# mt10.net
KiCad netlist of a schematic drawn in EAGLE
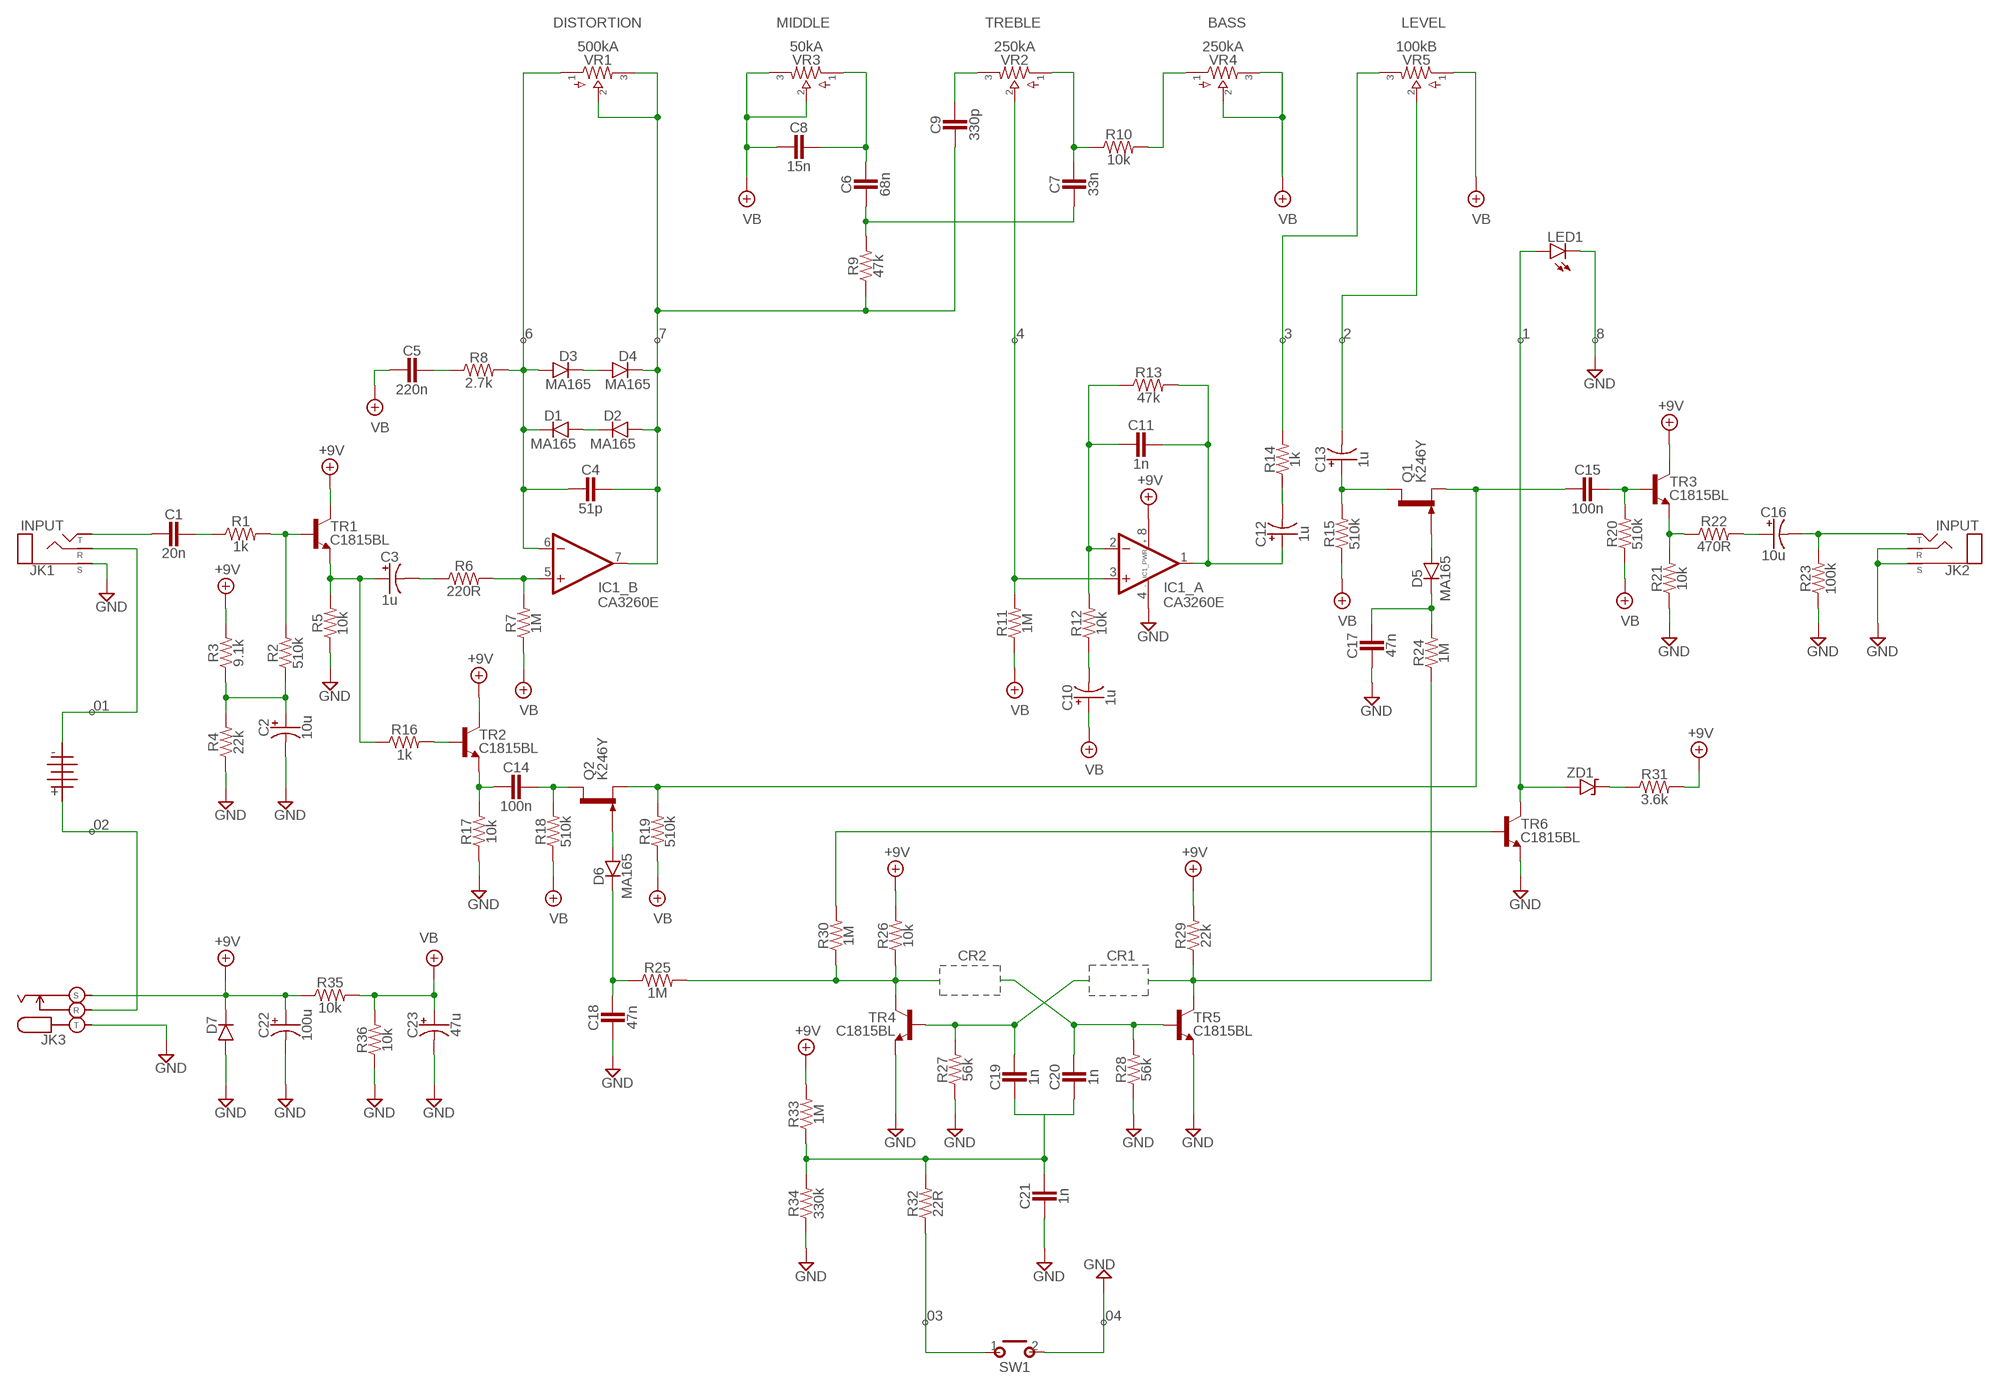
[diagram p0: schematic, sheet 1]

(export (version "E")
  (design (tool "Eeschema 10.0.6"))
  (components
    (comp (ref "1101")
      (value "BATTERY")
      (footprint "eagle-import:TWO_PADS")
      (libsource (lib "eagle-import") (part "BATTERY"))
    )
    (comp (ref "C1")
      (value "20n")
      (footprint "eagle-import:BOX_SMALL")
      (libsource (lib "eagle-import") (part "CER/FILMBOX.1"))
    )
    (comp (ref "C2")
      (value "10u")
      (footprint "eagle-import:050_020")
      (libsource (lib "eagle-import") (part "0500"))
    )
    (comp (ref "C3")
      (value "1u")
      (footprint "eagle-import:050_020")
      (libsource (lib "eagle-import") (part "0500"))
    )
    (comp (ref "C4")
      (value "51p")
      (footprint "eagle-import:BOX_SMALL")
      (libsource (lib "eagle-import") (part "CER/FILMBOX.1"))
    )
    (comp (ref "C5")
      (value "220n")
      (footprint "eagle-import:BOX_SMALL")
      (libsource (lib "eagle-import") (part "CER/FILMBOX.1"))
    )
    (comp (ref "C6")
      (value "68n")
      (footprint "eagle-import:BOX_SMALL")
      (libsource (lib "eagle-import") (part "CER/FILMBOX.1"))
    )
    (comp (ref "C7")
      (value "33n")
      (footprint "eagle-import:BOX_SMALL")
      (libsource (lib "eagle-import") (part "CER/FILMBOX.1"))
    )
    (comp (ref "C8")
      (value "15n")
      (footprint "eagle-import:BOX_SMALL")
      (libsource (lib "eagle-import") (part "CER/FILMBOX.1"))
    )
    (comp (ref "C9")
      (value "330p")
      (footprint "eagle-import:BOX_SMALL")
      (libsource (lib "eagle-import") (part "CER/FILMBOX.1"))
    )
    (comp (ref "C10")
      (value "1u")
      (footprint "eagle-import:050_020")
      (libsource (lib "eagle-import") (part "0500"))
    )
    (comp (ref "C11")
      (value "1n")
      (footprint "eagle-import:BOX_SMALL")
      (libsource (lib "eagle-import") (part "CER/FILMBOX.1"))
    )
    (comp (ref "C12")
      (value "1u")
      (footprint "eagle-import:050_020")
      (libsource (lib "eagle-import") (part "0500"))
    )
    (comp (ref "C13")
      (value "1u")
      (footprint "eagle-import:050_020")
      (libsource (lib "eagle-import") (part "0500"))
    )
    (comp (ref "C14")
      (value "100n")
      (footprint "eagle-import:BOX_SMALL")
      (libsource (lib "eagle-import") (part "CER/FILMBOX.1"))
    )
    (comp (ref "C15")
      (value "100n")
      (footprint "eagle-import:BOX_SMALL")
      (libsource (lib "eagle-import") (part "CER/FILMBOX.1"))
    )
    (comp (ref "C16")
      (value "10u")
      (footprint "eagle-import:050_020")
      (libsource (lib "eagle-import") (part "0500"))
    )
    (comp (ref "C17")
      (value "47n")
      (footprint "eagle-import:BOX_SMALL")
      (libsource (lib "eagle-import") (part "CER/FILMBOX.1"))
    )
    (comp (ref "C18")
      (value "47n")
      (footprint "eagle-import:BOX_SMALL")
      (libsource (lib "eagle-import") (part "CER/FILMBOX.1"))
    )
    (comp (ref "C19")
      (value "1n")
      (footprint "eagle-import:BOX_SMALL")
      (libsource (lib "eagle-import") (part "CER/FILMBOX.1"))
    )
    (comp (ref "C20")
      (value "1n")
      (footprint "eagle-import:BOX_SMALL")
      (libsource (lib "eagle-import") (part "CER/FILMBOX.1"))
    )
    (comp (ref "C21")
      (value "1n")
      (footprint "eagle-import:BOX_SMALL")
      (libsource (lib "eagle-import") (part "CER/FILMBOX.1"))
    )
    (comp (ref "C22")
      (value "100u")
      (footprint "eagle-import:050_020")
      (libsource (lib "eagle-import") (part "0500"))
    )
    (comp (ref "C23")
      (value "47u")
      (footprint "eagle-import:050_020")
      (libsource (lib "eagle-import") (part "0500"))
    )
    (comp (ref "D1")
      (value "MA165")
      (footprint "eagle-import:DO35-2")
      (libsource (lib "eagle-import") (part "DO35.2"))
    )
    (comp (ref "D2")
      (value "MA165")
      (footprint "eagle-import:DO35-2")
      (libsource (lib "eagle-import") (part "DO35.2"))
    )
    (comp (ref "D3")
      (value "MA165")
      (footprint "eagle-import:DO35-2")
      (libsource (lib "eagle-import") (part "DO35.2"))
    )
    (comp (ref "D4")
      (value "MA165")
      (footprint "eagle-import:DO35-2")
      (libsource (lib "eagle-import") (part "DO35.2"))
    )
    (comp (ref "D5")
      (value "MA165")
      (footprint "eagle-import:DO35-2")
      (libsource (lib "eagle-import") (part "DO35.2"))
    )
    (comp (ref "D6")
      (value "MA165")
      (footprint "eagle-import:DO35-2")
      (libsource (lib "eagle-import") (part "DO35.2"))
    )
    (comp (ref "D7")
      (value "DO35.2")
      (footprint "eagle-import:DO35-2")
      (libsource (lib "eagle-import") (part "DO35.2"))
    )
    (comp (ref "IC1")
      (value "CA3260E")
      (footprint "eagle-import:DIL0")
      (libsource (lib "eagle-import") (part "DUALTH"))
    )
    (comp (ref "JK1")
      (value "INPUT")
      (footprint "eagle-import:THREEPADS")
      (libsource (lib "eagle-import") (part "STEREO3PADS"))
    )
    (comp (ref "JK2")
      (value "INPUT")
      (footprint "eagle-import:THREEPADS")
      (libsource (lib "eagle-import") (part "STEREO3PADS"))
    )
    (comp (ref "JK3")
      (value "DCJACK")
      (footprint "eagle-import:DC_KOBICONN")
      (libsource (lib "eagle-import") (part "DC_KOBICONN"))
    )
    (comp (ref "LED1")
      (value "LED")
      (footprint "eagle-import:3MM_D")
      (libsource (lib "eagle-import") (part "LED"))
    )
    (comp (ref "Q1")
      (value "K246Y")
      (footprint "eagle-import:TO92-")
      (libsource (lib "eagle-import") (part "2N5457"))
    )
    (comp (ref "Q2")
      (value "K246Y")
      (footprint "eagle-import:TO92-")
      (libsource (lib "eagle-import") (part "2N5457"))
    )
    (comp (ref "R1")
      (value "1k")
      (footprint "eagle-import:R0207_3")
      (libsource (lib "eagle-import") (part "R_.3B"))
    )
    (comp (ref "R2")
      (value "510k")
      (footprint "eagle-import:R0207_3")
      (libsource (lib "eagle-import") (part "R_.3B"))
    )
    (comp (ref "R3")
      (value "9.1k")
      (footprint "eagle-import:R0207_3")
      (libsource (lib "eagle-import") (part "R_.3B"))
    )
    (comp (ref "R4")
      (value "22k")
      (footprint "eagle-import:R0207_3")
      (libsource (lib "eagle-import") (part "R_.3B"))
    )
    (comp (ref "R5")
      (value "10k")
      (footprint "eagle-import:R0207_3")
      (libsource (lib "eagle-import") (part "R_.3B"))
    )
    (comp (ref "R6")
      (value "220R")
      (footprint "eagle-import:R0207_3")
      (libsource (lib "eagle-import") (part "R_.3B"))
    )
    (comp (ref "R7")
      (value "1M")
      (footprint "eagle-import:R0207_3")
      (libsource (lib "eagle-import") (part "R_.3B"))
    )
    (comp (ref "R8")
      (value "2.7k")
      (footprint "eagle-import:R0207_3")
      (libsource (lib "eagle-import") (part "R_.3B"))
    )
    (comp (ref "R9")
      (value "47k")
      (footprint "eagle-import:R0207_3")
      (libsource (lib "eagle-import") (part "R_.3B"))
    )
    (comp (ref "R10")
      (value "10k")
      (footprint "eagle-import:R0207_3")
      (libsource (lib "eagle-import") (part "R_.3B"))
    )
    (comp (ref "R11")
      (value "1M")
      (footprint "eagle-import:R0207_3")
      (libsource (lib "eagle-import") (part "R_.3B"))
    )
    (comp (ref "R12")
      (value "10k")
      (footprint "eagle-import:R0207_3")
      (libsource (lib "eagle-import") (part "R_.3B"))
    )
    (comp (ref "R13")
      (value "47k")
      (footprint "eagle-import:R0207_3")
      (libsource (lib "eagle-import") (part "R_.3B"))
    )
    (comp (ref "R14")
      (value "1k")
      (footprint "eagle-import:R0207_3")
      (libsource (lib "eagle-import") (part "R_.3B"))
    )
    (comp (ref "R15")
      (value "510k")
      (footprint "eagle-import:R0207_3")
      (libsource (lib "eagle-import") (part "R_.3B"))
    )
    (comp (ref "R16")
      (value "1k")
      (footprint "eagle-import:R0207_3")
      (libsource (lib "eagle-import") (part "R_.3B"))
    )
    (comp (ref "R17")
      (value "10k")
      (footprint "eagle-import:R0207_3")
      (libsource (lib "eagle-import") (part "R_.3B"))
    )
    (comp (ref "R18")
      (value "510k")
      (footprint "eagle-import:R0207_3")
      (libsource (lib "eagle-import") (part "R_.3B"))
    )
    (comp (ref "R19")
      (value "510k")
      (footprint "eagle-import:R0207_3")
      (libsource (lib "eagle-import") (part "R_.3B"))
    )
    (comp (ref "R20")
      (value "510k")
      (footprint "eagle-import:R0207_3")
      (libsource (lib "eagle-import") (part "R_.3B"))
    )
    (comp (ref "R21")
      (value "10k")
      (footprint "eagle-import:R0207_3")
      (libsource (lib "eagle-import") (part "R_.3B"))
    )
    (comp (ref "R22")
      (value "470R")
      (footprint "eagle-import:R0207_3")
      (libsource (lib "eagle-import") (part "R_.3B"))
    )
    (comp (ref "R23")
      (value "100k")
      (footprint "eagle-import:R0207_3")
      (libsource (lib "eagle-import") (part "R_.3B"))
    )
    (comp (ref "R24")
      (value "1M")
      (footprint "eagle-import:R0207_3")
      (libsource (lib "eagle-import") (part "R_.3B"))
    )
    (comp (ref "R25")
      (value "1M")
      (footprint "eagle-import:R0207_3")
      (libsource (lib "eagle-import") (part "R_.3B"))
    )
    (comp (ref "R26")
      (value "10k")
      (footprint "eagle-import:R0207_3")
      (libsource (lib "eagle-import") (part "R_.3B"))
    )
    (comp (ref "R27")
      (value "56k")
      (footprint "eagle-import:R0207_3")
      (libsource (lib "eagle-import") (part "R_.3B"))
    )
    (comp (ref "R28")
      (value "56k")
      (footprint "eagle-import:R0207_3")
      (libsource (lib "eagle-import") (part "R_.3B"))
    )
    (comp (ref "R29")
      (value "22k")
      (footprint "eagle-import:R0207_3")
      (libsource (lib "eagle-import") (part "R_.3B"))
    )
    (comp (ref "R30")
      (value "1M")
      (footprint "eagle-import:R0207_3")
      (libsource (lib "eagle-import") (part "R_.3B"))
    )
    (comp (ref "R31")
      (value "3.6k")
      (footprint "eagle-import:R0207_3")
      (libsource (lib "eagle-import") (part "R_.3B"))
    )
    (comp (ref "R32")
      (value "22R")
      (footprint "eagle-import:R0207_3")
      (libsource (lib "eagle-import") (part "R_.3B"))
    )
    (comp (ref "R33")
      (value "1M")
      (footprint "eagle-import:R0207_3")
      (libsource (lib "eagle-import") (part "R_.3B"))
    )
    (comp (ref "R34")
      (value "330k")
      (footprint "eagle-import:R0207_3")
      (libsource (lib "eagle-import") (part "R_.3B"))
    )
    (comp (ref "R35")
      (value "10k")
      (footprint "eagle-import:R0207_3")
      (libsource (lib "eagle-import") (part "R_.3B"))
    )
    (comp (ref "R36")
      (value "10k")
      (footprint "eagle-import:R0207_3")
      (libsource (lib "eagle-import") (part "R_.3B"))
    )
    (comp (ref "SW1")
      (value "MOMENTARY")
      (footprint "eagle-import:SPST")
      (libsource (lib "eagle-import") (part "MOMENTARY"))
    )
    (comp (ref "TR1")
      (value "C1815BL")
      (footprint "eagle-import:TO92-")
      (libsource (lib "eagle-import") (part "2SC828A"))
    )
    (comp (ref "TR2")
      (value "C1815BL")
      (footprint "eagle-import:TO92-")
      (libsource (lib "eagle-import") (part "2SC828A"))
    )
    (comp (ref "TR3")
      (value "C1815BL")
      (footprint "eagle-import:TO92-")
      (libsource (lib "eagle-import") (part "2SC828A"))
    )
    (comp (ref "TR4")
      (value "C1815BL")
      (footprint "eagle-import:TO92-")
      (libsource (lib "eagle-import") (part "2SC828A"))
    )
    (comp (ref "TR5")
      (value "C1815BL")
      (footprint "eagle-import:TO92-")
      (libsource (lib "eagle-import") (part "2SC828A"))
    )
    (comp (ref "TR6")
      (value "C1815BL")
      (footprint "eagle-import:TO92-")
      (libsource (lib "eagle-import") (part "2SC828A"))
    )
    (comp (ref "VR1")
      (value "500kA")
      (footprint "eagle-import:16MM")
      (libsource (lib "eagle-import") (part "POTS16MM"))
    )
    (comp (ref "VR2")
      (value "250kA")
      (footprint "eagle-import:16MM")
      (libsource (lib "eagle-import") (part "POTS16MM"))
    )
    (comp (ref "VR3")
      (value "50kA")
      (footprint "eagle-import:16MM")
      (libsource (lib "eagle-import") (part "POTS16MM"))
    )
    (comp (ref "VR4")
      (value "250kA")
      (footprint "eagle-import:16MM")
      (libsource (lib "eagle-import") (part "POTS16MM"))
    )
    (comp (ref "VR5")
      (value "100kB")
      (footprint "eagle-import:16MM")
      (libsource (lib "eagle-import") (part "POTS16MM"))
    )
    (comp (ref "ZD1")
      (value "ZENER.1")
      (footprint "eagle-import:DO41-1")
      (libsource (lib "eagle-import") (part "ZENER.1"))
    )
  )
  (nets
    (net (code "1") (name "+9V") (class "Default")
      (node (ref "C22") (pin "+") (pinfunction "+_+") (pintype "passive"))
      (node (ref "D7") (pin "C") (pinfunction "C_C") (pintype "passive"))
      (node (ref "IC1") (pin "8") (pinfunction "V+_8") (pintype "power_in"))
      (node (ref "JK3") (pin "S") (pinfunction "S_S") (pintype "bidirectional"))
      (node (ref "R26") (pin "2") (pinfunction "2_2") (pintype "passive"))
      (node (ref "R29") (pin "2") (pinfunction "2_2") (pintype "passive"))
      (node (ref "R3") (pin "2") (pinfunction "2_2") (pintype "passive"))
      (node (ref "R31") (pin "2") (pinfunction "2_2") (pintype "passive"))
      (node (ref "R33") (pin "2") (pinfunction "2_2") (pintype "passive"))
      (node (ref "R35") (pin "1") (pinfunction "1_1") (pintype "passive"))
      (node (ref "TR1") (pin "2") (pinfunction "C_2") (pintype "passive"))
      (node (ref "TR2") (pin "2") (pinfunction "C_2") (pintype "passive"))
      (node (ref "TR3") (pin "2") (pinfunction "C_2") (pintype "passive"))
    )
    (net (code "2") (name "GND") (class "Default")
      (node (ref "C17") (pin "2") (pinfunction "2_2") (pintype "passive"))
      (node (ref "C18") (pin "2") (pinfunction "2_2") (pintype "passive"))
      (node (ref "C2") (pin "-") (pinfunction "-_-") (pintype "passive"))
      (node (ref "C21") (pin "2") (pinfunction "2_2") (pintype "passive"))
      (node (ref "C22") (pin "-") (pinfunction "-_-") (pintype "passive"))
      (node (ref "C23") (pin "-") (pinfunction "-_-") (pintype "passive"))
      (node (ref "D7") (pin "A") (pinfunction "A_A") (pintype "passive"))
      (node (ref "IC1") (pin "4") (pinfunction "V-_4") (pintype "power_in"))
      (node (ref "JK1") (pin "SLEEVE") (pinfunction "S_SLEEVE") (pintype "passive"))
      (node (ref "JK2") (pin "RING") (pinfunction "R_RING") (pintype "passive"))
      (node (ref "JK2") (pin "SLEEVE") (pinfunction "S_SLEEVE") (pintype "passive"))
      (node (ref "JK3") (pin "T") (pinfunction "T_T") (pintype "bidirectional"))
      (node (ref "LED1") (pin "P$1") (pinfunction "C_P$1") (pintype "passive"))
      (node (ref "R17") (pin "1") (pinfunction "1_1") (pintype "passive"))
      (node (ref "R21") (pin "1") (pinfunction "1_1") (pintype "passive"))
      (node (ref "R23") (pin "1") (pinfunction "1_1") (pintype "passive"))
      (node (ref "R27") (pin "1") (pinfunction "1_1") (pintype "passive"))
      (node (ref "R28") (pin "1") (pinfunction "1_1") (pintype "passive"))
      (node (ref "R34") (pin "1") (pinfunction "1_1") (pintype "passive"))
      (node (ref "R36") (pin "1") (pinfunction "1_1") (pintype "passive"))
      (node (ref "R4") (pin "1") (pinfunction "1_1") (pintype "passive"))
      (node (ref "R5") (pin "1") (pinfunction "1_1") (pintype "passive"))
      (node (ref "SW1") (pin "2") (pinfunction "S_2") (pintype "passive"))
      (node (ref "TR4") (pin "3") (pinfunction "E_3") (pintype "passive"))
      (node (ref "TR5") (pin "3") (pinfunction "E_3") (pintype "passive"))
      (node (ref "TR6") (pin "3") (pinfunction "E_3") (pintype "passive"))
    )
    (net (code "3") (name "Net-(1101-P$1)") (class "Default")
      (node (ref "1101") (pin "T") (pinfunction "P$1_T") (pintype "bidirectional"))
      (node (ref "JK3") (pin "R") (pinfunction "R_R") (pintype "bidirectional"))
    )
    (net (code "4") (name "Net-(1101-P$2)") (class "Default")
      (node (ref "1101") (pin "S") (pinfunction "P$2_S") (pintype "bidirectional"))
      (node (ref "JK1") (pin "RING") (pinfunction "R_RING") (pintype "passive"))
    )
    (net (code "5") (name "Net-(C1-Pad1)") (class "Default")
      (node (ref "C1") (pin "1") (pinfunction "1_1") (pintype "passive"))
      (node (ref "R1") (pin "1") (pinfunction "1_1") (pintype "passive"))
    )
    (net (code "6") (name "Net-(C2-Pad+)") (class "Default")
      (node (ref "C2") (pin "+") (pinfunction "+_+") (pintype "passive"))
      (node (ref "R2") (pin "1") (pinfunction "1_1") (pintype "passive"))
      (node (ref "R3") (pin "1") (pinfunction "1_1") (pintype "passive"))
      (node (ref "R4") (pin "2") (pinfunction "2_2") (pintype "passive"))
    )
    (net (code "7") (name "Net-(C3-Pad-)") (class "Default")
      (node (ref "C3") (pin "-") (pinfunction "-_-") (pintype "passive"))
      (node (ref "R6") (pin "1") (pinfunction "1_1") (pintype "passive"))
    )
    (net (code "8") (name "Net-(C5-Pad1)") (class "Default")
      (node (ref "C5") (pin "1") (pinfunction "1_1") (pintype "passive"))
      (node (ref "R8") (pin "1") (pinfunction "1_1") (pintype "passive"))
    )
    (net (code "9") (name "Net-(C6-Pad1)") (class "Default")
      (node (ref "C6") (pin "1") (pinfunction "1_1") (pintype "passive"))
      (node (ref "C8") (pin "1") (pinfunction "1_1") (pintype "passive"))
      (node (ref "VR3") (pin "1") (pinfunction "1_1") (pintype "passive"))
    )
    (net (code "10") (name "Net-(C6-Pad2)") (class "Default")
      (node (ref "C6") (pin "2") (pinfunction "2_2") (pintype "passive"))
      (node (ref "C7") (pin "2") (pinfunction "2_2") (pintype "passive"))
      (node (ref "R9") (pin "2") (pinfunction "2_2") (pintype "passive"))
    )
    (net (code "11") (name "Net-(C7-Pad1)") (class "Default")
      (node (ref "C7") (pin "1") (pinfunction "1_1") (pintype "passive"))
      (node (ref "R10") (pin "1") (pinfunction "1_1") (pintype "passive"))
      (node (ref "VR2") (pin "1") (pinfunction "1_1") (pintype "passive"))
    )
    (net (code "12") (name "Net-(C9-Pad1)") (class "Default")
      (node (ref "C9") (pin "1") (pinfunction "1_1") (pintype "passive"))
      (node (ref "VR2") (pin "3") (pinfunction "3_3") (pintype "passive"))
    )
    (net (code "13") (name "Net-(C10-Pad-)") (class "Default")
      (node (ref "C10") (pin "-") (pinfunction "-_-") (pintype "passive"))
      (node (ref "R12") (pin "1") (pinfunction "1_1") (pintype "passive"))
    )
    (net (code "14") (name "Net-(C12-Pad-)") (class "Default")
      (node (ref "C12") (pin "-") (pinfunction "-_-") (pintype "passive"))
      (node (ref "R14") (pin "1") (pinfunction "1_1") (pintype "passive"))
    )
    (net (code "15") (name "Net-(C13-Pad-)") (class "Default")
      (node (ref "C13") (pin "-") (pinfunction "-_-") (pintype "passive"))
      (node (ref "VR5") (pin "2") (pinfunction "2_2") (pintype "passive"))
    )
    (net (code "16") (name "Net-(C16-Pad+)") (class "Default")
      (node (ref "C16") (pin "+") (pinfunction "+_+") (pintype "passive"))
      (node (ref "R22") (pin "2") (pinfunction "2_2") (pintype "passive"))
    )
    (net (code "17") (name "Net-(C17-Pad1)") (class "Default")
      (node (ref "C17") (pin "1") (pinfunction "1_1") (pintype "passive"))
      (node (ref "D5") (pin "C") (pinfunction "C_C") (pintype "passive"))
      (node (ref "R24") (pin "2") (pinfunction "2_2") (pintype "passive"))
    )
    (net (code "18") (name "Net-(C18-Pad1)") (class "Default")
      (node (ref "C18") (pin "1") (pinfunction "1_1") (pintype "passive"))
      (node (ref "D6") (pin "C") (pinfunction "C_C") (pintype "passive"))
      (node (ref "R25") (pin "1") (pinfunction "1_1") (pintype "passive"))
    )
    (net (code "19") (name "Net-(C19-Pad2)") (class "Default")
      (node (ref "C19") (pin "2") (pinfunction "2_2") (pintype "passive"))
      (node (ref "C20") (pin "2") (pinfunction "2_2") (pintype "passive"))
      (node (ref "C21") (pin "1") (pinfunction "1_1") (pintype "passive"))
      (node (ref "R32") (pin "2") (pinfunction "2_2") (pintype "passive"))
      (node (ref "R33") (pin "1") (pinfunction "1_1") (pintype "passive"))
      (node (ref "R34") (pin "2") (pinfunction "2_2") (pintype "passive"))
    )
    (net (code "20") (name "Net-(D1-PadA)") (class "Default")
      (node (ref "D1") (pin "A") (pinfunction "A_A") (pintype "passive"))
      (node (ref "D2") (pin "C") (pinfunction "C_C") (pintype "passive"))
    )
    (net (code "21") (name "Net-(D3-PadC)") (class "Default")
      (node (ref "D3") (pin "C") (pinfunction "C_C") (pintype "passive"))
      (node (ref "D4") (pin "A") (pinfunction "A_A") (pintype "passive"))
    )
    (net (code "22") (name "Net-(IC1A-+IN)") (class "Default")
      (node (ref "IC1") (pin "3") (pinfunction "+IN_3") (pintype "input"))
      (node (ref "R11") (pin "2") (pinfunction "2_2") (pintype "passive"))
      (node (ref "VR2") (pin "2") (pinfunction "2_2") (pintype "passive"))
    )
    (net (code "23") (name "Net-(IC1A--IN)") (class "Default")
      (node (ref "C11") (pin "2") (pinfunction "2_2") (pintype "passive"))
      (node (ref "IC1") (pin "2") (pinfunction "-IN_2") (pintype "input"))
      (node (ref "R12") (pin "2") (pinfunction "2_2") (pintype "passive"))
      (node (ref "R13") (pin "1") (pinfunction "1_1") (pintype "passive"))
    )
    (net (code "24") (name "Net-(IC1A-OUT)") (class "Default")
      (node (ref "C11") (pin "1") (pinfunction "1_1") (pintype "passive"))
      (node (ref "C12") (pin "+") (pinfunction "+_+") (pintype "passive"))
      (node (ref "IC1") (pin "1") (pinfunction "OUT_1") (pintype "output"))
      (node (ref "R13") (pin "2") (pinfunction "2_2") (pintype "passive"))
    )
    (net (code "25") (name "Net-(IC1B-+IN)") (class "Default")
      (node (ref "IC1") (pin "5") (pinfunction "+IN_5") (pintype "input"))
      (node (ref "R6") (pin "2") (pinfunction "2_2") (pintype "passive"))
      (node (ref "R7") (pin "2") (pinfunction "2_2") (pintype "passive"))
    )
    (net (code "26") (name "Net-(IC1B--IN)") (class "Default")
      (node (ref "C4") (pin "2") (pinfunction "2_2") (pintype "passive"))
      (node (ref "D1") (pin "C") (pinfunction "C_C") (pintype "passive"))
      (node (ref "D3") (pin "A") (pinfunction "A_A") (pintype "passive"))
      (node (ref "IC1") (pin "6") (pinfunction "-IN_6") (pintype "input"))
      (node (ref "R8") (pin "2") (pinfunction "2_2") (pintype "passive"))
      (node (ref "VR1") (pin "1") (pinfunction "1_1") (pintype "passive"))
    )
    (net (code "27") (name "Net-(IC1B-OUT)") (class "Default")
      (node (ref "C4") (pin "1") (pinfunction "1_1") (pintype "passive"))
      (node (ref "C9") (pin "2") (pinfunction "2_2") (pintype "passive"))
      (node (ref "D2") (pin "A") (pinfunction "A_A") (pintype "passive"))
      (node (ref "D4") (pin "C") (pinfunction "C_C") (pintype "passive"))
      (node (ref "IC1") (pin "7") (pinfunction "OUT_7") (pintype "output"))
      (node (ref "R9") (pin "1") (pinfunction "1_1") (pintype "passive"))
      (node (ref "VR1") (pin "2") (pinfunction "2_2") (pintype "passive"))
      (node (ref "VR1") (pin "3") (pinfunction "3_3") (pintype "passive"))
    )
    (net (code "28") (name "Net-(JK1-T)") (class "Default")
      (node (ref "C1") (pin "2") (pinfunction "2_2") (pintype "passive"))
      (node (ref "JK1") (pin "TIP") (pinfunction "T_TIP") (pintype "passive"))
    )
    (net (code "29") (name "Net-(JK2-T)") (class "Default")
      (node (ref "C16") (pin "-") (pinfunction "-_-") (pintype "passive"))
      (node (ref "JK2") (pin "TIP") (pinfunction "T_TIP") (pintype "passive"))
      (node (ref "R23") (pin "2") (pinfunction "2_2") (pintype "passive"))
    )
    (net (code "30") (name "Net-(LED1-A)") (class "Default")
      (node (ref "LED1") (pin "ANODE") (pinfunction "A_ANODE") (pintype "passive"))
      (node (ref "TR6") (pin "2") (pinfunction "C_2") (pintype "passive"))
      (node (ref "ZD1") (pin "A") (pinfunction "A_A") (pintype "passive"))
    )
    (net (code "31") (name "Net-(Q1-D)") (class "Default")
      (node (ref "C13") (pin "+") (pinfunction "+_+") (pintype "passive"))
      (node (ref "Q1") (pin "3") (pinfunction "D_3") (pintype "passive"))
      (node (ref "R15") (pin "2") (pinfunction "2_2") (pintype "passive"))
    )
    (net (code "32") (name "Net-(Q1-G)") (class "Default")
      (node (ref "D5") (pin "A") (pinfunction "A_A") (pintype "passive"))
      (node (ref "Q1") (pin "1") (pinfunction "G_1") (pintype "passive"))
    )
    (net (code "33") (name "Net-(Q1-S)") (class "Default")
      (node (ref "C15") (pin "2") (pinfunction "2_2") (pintype "passive"))
      (node (ref "Q1") (pin "2") (pinfunction "S_2") (pintype "passive"))
      (node (ref "Q2") (pin "2") (pinfunction "S_2") (pintype "passive"))
      (node (ref "R19") (pin "2") (pinfunction "2_2") (pintype "passive"))
    )
    (net (code "34") (name "Net-(Q2-D)") (class "Default")
      (node (ref "C14") (pin "1") (pinfunction "1_1") (pintype "passive"))
      (node (ref "Q2") (pin "3") (pinfunction "D_3") (pintype "passive"))
      (node (ref "R18") (pin "2") (pinfunction "2_2") (pintype "passive"))
    )
    (net (code "35") (name "Net-(Q2-G)") (class "Default")
      (node (ref "D6") (pin "A") (pinfunction "A_A") (pintype "passive"))
      (node (ref "Q2") (pin "1") (pinfunction "G_1") (pintype "passive"))
    )
    (net (code "36") (name "Net-(R10-Pad2)") (class "Default")
      (node (ref "R10") (pin "2") (pinfunction "2_2") (pintype "passive"))
      (node (ref "VR4") (pin "1") (pinfunction "1_1") (pintype "passive"))
    )
    (net (code "37") (name "Net-(R14-Pad2)") (class "Default")
      (node (ref "R14") (pin "2") (pinfunction "2_2") (pintype "passive"))
      (node (ref "VR5") (pin "3") (pinfunction "3_3") (pintype "passive"))
    )
    (net (code "38") (name "Net-(R31-Pad1)") (class "Default")
      (node (ref "R31") (pin "1") (pinfunction "1_1") (pintype "passive"))
      (node (ref "ZD1") (pin "C") (pinfunction "C_C") (pintype "passive"))
    )
    (net (code "39") (name "Net-(SW1-P)") (class "Default")
      (node (ref "R32") (pin "1") (pinfunction "1_1") (pintype "passive"))
      (node (ref "SW1") (pin "1") (pinfunction "P_1") (pintype "passive"))
    )
    (net (code "40") (name "Net-(TR1-B)") (class "Default")
      (node (ref "R1") (pin "2") (pinfunction "2_2") (pintype "passive"))
      (node (ref "R2") (pin "2") (pinfunction "2_2") (pintype "passive"))
      (node (ref "TR1") (pin "1") (pinfunction "B_1") (pintype "passive"))
    )
    (net (code "41") (name "Net-(TR1-E)") (class "Default")
      (node (ref "C3") (pin "+") (pinfunction "+_+") (pintype "passive"))
      (node (ref "R16") (pin "1") (pinfunction "1_1") (pintype "passive"))
      (node (ref "R5") (pin "2") (pinfunction "2_2") (pintype "passive"))
      (node (ref "TR1") (pin "3") (pinfunction "E_3") (pintype "passive"))
    )
    (net (code "42") (name "Net-(TR2-B)") (class "Default")
      (node (ref "R16") (pin "2") (pinfunction "2_2") (pintype "passive"))
      (node (ref "TR2") (pin "1") (pinfunction "B_1") (pintype "passive"))
    )
    (net (code "43") (name "Net-(TR2-E)") (class "Default")
      (node (ref "C14") (pin "2") (pinfunction "2_2") (pintype "passive"))
      (node (ref "R17") (pin "2") (pinfunction "2_2") (pintype "passive"))
      (node (ref "TR2") (pin "3") (pinfunction "E_3") (pintype "passive"))
    )
    (net (code "44") (name "Net-(TR3-B)") (class "Default")
      (node (ref "C15") (pin "1") (pinfunction "1_1") (pintype "passive"))
      (node (ref "R20") (pin "2") (pinfunction "2_2") (pintype "passive"))
      (node (ref "TR3") (pin "1") (pinfunction "B_1") (pintype "passive"))
    )
    (net (code "45") (name "Net-(TR3-E)") (class "Default")
      (node (ref "R21") (pin "2") (pinfunction "2_2") (pintype "passive"))
      (node (ref "R22") (pin "1") (pinfunction "1_1") (pintype "passive"))
      (node (ref "TR3") (pin "3") (pinfunction "E_3") (pintype "passive"))
    )
    (net (code "46") (name "Net-(TR4-B)") (class "Default")
      (node (ref "C19") (pin "1") (pinfunction "1_1") (pintype "passive"))
      (node (ref "R27") (pin "2") (pinfunction "2_2") (pintype "passive"))
      (node (ref "TR4") (pin "1") (pinfunction "B_1") (pintype "passive"))
    )
    (net (code "47") (name "Net-(TR4-C)") (class "Default")
      (node (ref "R25") (pin "2") (pinfunction "2_2") (pintype "passive"))
      (node (ref "R26") (pin "1") (pinfunction "1_1") (pintype "passive"))
      (node (ref "R30") (pin "1") (pinfunction "1_1") (pintype "passive"))
      (node (ref "TR4") (pin "2") (pinfunction "C_2") (pintype "passive"))
    )
    (net (code "48") (name "Net-(TR5-B)") (class "Default")
      (node (ref "C20") (pin "1") (pinfunction "1_1") (pintype "passive"))
      (node (ref "R28") (pin "2") (pinfunction "2_2") (pintype "passive"))
      (node (ref "TR5") (pin "1") (pinfunction "B_1") (pintype "passive"))
    )
    (net (code "49") (name "Net-(TR5-C)") (class "Default")
      (node (ref "R24") (pin "1") (pinfunction "1_1") (pintype "passive"))
      (node (ref "R29") (pin "1") (pinfunction "1_1") (pintype "passive"))
      (node (ref "TR5") (pin "2") (pinfunction "C_2") (pintype "passive"))
    )
    (net (code "50") (name "Net-(TR6-B)") (class "Default")
      (node (ref "R30") (pin "2") (pinfunction "2_2") (pintype "passive"))
      (node (ref "TR6") (pin "1") (pinfunction "B_1") (pintype "passive"))
    )
    (net (code "51") (name "VB") (class "Default")
      (node (ref "C10") (pin "+") (pinfunction "+_+") (pintype "passive"))
      (node (ref "C23") (pin "+") (pinfunction "+_+") (pintype "passive"))
      (node (ref "C5") (pin "2") (pinfunction "2_2") (pintype "passive"))
      (node (ref "C8") (pin "2") (pinfunction "2_2") (pintype "passive"))
      (node (ref "R11") (pin "1") (pinfunction "1_1") (pintype "passive"))
      (node (ref "R15") (pin "1") (pinfunction "1_1") (pintype "passive"))
      (node (ref "R18") (pin "1") (pinfunction "1_1") (pintype "passive"))
      (node (ref "R19") (pin "1") (pinfunction "1_1") (pintype "passive"))
      (node (ref "R20") (pin "1") (pinfunction "1_1") (pintype "passive"))
      (node (ref "R35") (pin "2") (pinfunction "2_2") (pintype "passive"))
      (node (ref "R36") (pin "2") (pinfunction "2_2") (pintype "passive"))
      (node (ref "R7") (pin "1") (pinfunction "1_1") (pintype "passive"))
      (node (ref "VR3") (pin "2") (pinfunction "2_2") (pintype "passive"))
      (node (ref "VR3") (pin "3") (pinfunction "3_3") (pintype "passive"))
      (node (ref "VR4") (pin "2") (pinfunction "2_2") (pintype "passive"))
      (node (ref "VR4") (pin "3") (pinfunction "3_3") (pintype "passive"))
      (node (ref "VR5") (pin "1") (pinfunction "1_1") (pintype "passive"))
    )
  )
)
